# main_v4.net
KiCad netlist of a schematic drawn in EAGLE
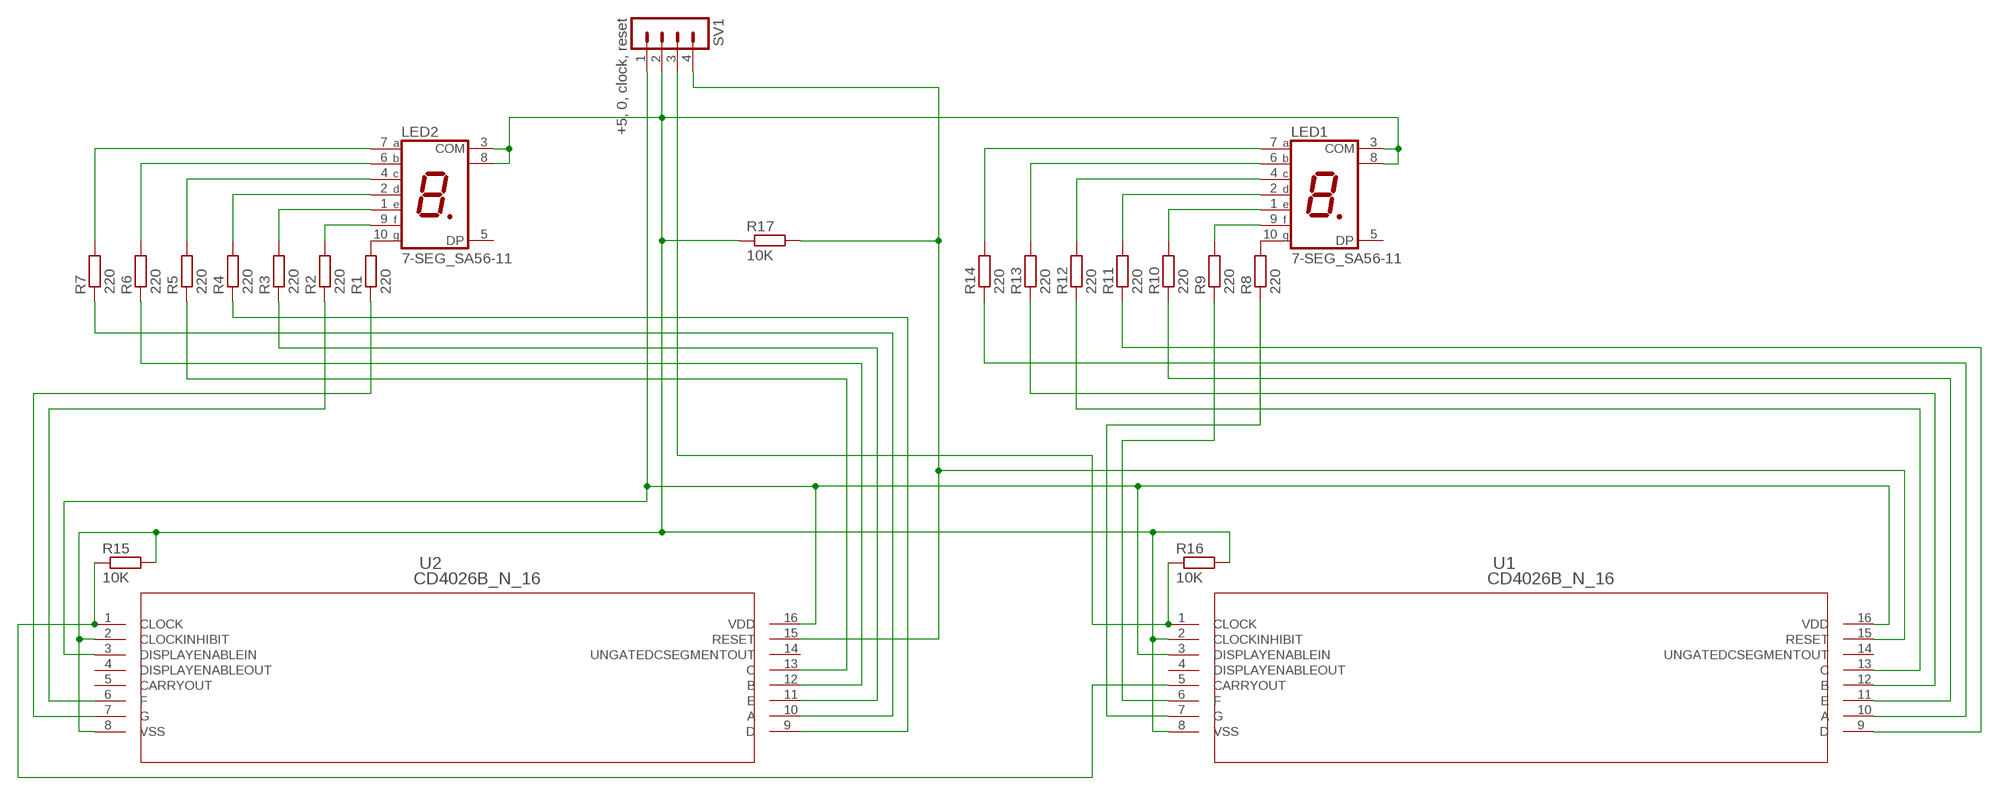
[diagram p0: schematic, sheet 1]

(export (version "E")
  (design (tool "Eeschema 10.0.6"))
  (components
    (comp (ref "LED1")
      (value "7-SEG_SA56-11")
      (footprint "eagle-import:SA56-11")
      (libsource (lib "eagle-import") (part "7-SEG_SA56-11"))
    )
    (comp (ref "LED2")
      (value "7-SEG_SA56-11")
      (footprint "eagle-import:SA56-11")
      (libsource (lib "eagle-import") (part "7-SEG_SA56-11"))
    )
    (comp (ref "R1")
      (value "220")
      (footprint "eagle-import:R0805")
      (libsource (lib "eagle-import") (part "R-EU_R0805"))
    )
    (comp (ref "R2")
      (value "220")
      (footprint "eagle-import:R0805")
      (libsource (lib "eagle-import") (part "R-EU_R0805"))
    )
    (comp (ref "R3")
      (value "220")
      (footprint "eagle-import:R0805")
      (libsource (lib "eagle-import") (part "R-EU_R0805"))
    )
    (comp (ref "R4")
      (value "220")
      (footprint "eagle-import:R0805")
      (libsource (lib "eagle-import") (part "R-EU_R0805"))
    )
    (comp (ref "R5")
      (value "220")
      (footprint "eagle-import:R0805")
      (libsource (lib "eagle-import") (part "R-EU_R0805"))
    )
    (comp (ref "R6")
      (value "220")
      (footprint "eagle-import:R0805")
      (libsource (lib "eagle-import") (part "R-EU_R0805"))
    )
    (comp (ref "R7")
      (value "220")
      (footprint "eagle-import:R0805")
      (libsource (lib "eagle-import") (part "R-EU_R0805"))
    )
    (comp (ref "R8")
      (value "220")
      (footprint "eagle-import:R0805")
      (libsource (lib "eagle-import") (part "R-EU_R0805"))
    )
    (comp (ref "R9")
      (value "220")
      (footprint "eagle-import:R0805")
      (libsource (lib "eagle-import") (part "R-EU_R0805"))
    )
    (comp (ref "R10")
      (value "220")
      (footprint "eagle-import:R0805")
      (libsource (lib "eagle-import") (part "R-EU_R0805"))
    )
    (comp (ref "R11")
      (value "220")
      (footprint "eagle-import:R0805")
      (libsource (lib "eagle-import") (part "R-EU_R0805"))
    )
    (comp (ref "R12")
      (value "220")
      (footprint "eagle-import:R0805")
      (libsource (lib "eagle-import") (part "R-EU_R0805"))
    )
    (comp (ref "R13")
      (value "220")
      (footprint "eagle-import:R0805")
      (libsource (lib "eagle-import") (part "R-EU_R0805"))
    )
    (comp (ref "R14")
      (value "220")
      (footprint "eagle-import:R0805")
      (libsource (lib "eagle-import") (part "R-EU_R0805"))
    )
    (comp (ref "R15")
      (value "10K")
      (footprint "eagle-import:R0805")
      (libsource (lib "eagle-import") (part "R-EU_R0805"))
    )
    (comp (ref "R16")
      (value "10K")
      (footprint "eagle-import:R0805")
      (libsource (lib "eagle-import") (part "R-EU_R0805"))
    )
    (comp (ref "R17")
      (value "10K")
      (footprint "eagle-import:R0805")
      (libsource (lib "eagle-import") (part "R-EU_R0805"))
    )
    (comp (ref "SV1")
      (value "+5, 0, clock, reset")
      (footprint "eagle-import:MA04-1")
      (libsource (lib "eagle-import") (part "MA04-1"))
    )
    (comp (ref "U1")
      (value "CD4026B_N_16")
      (footprint "eagle-import:N16")
      (fields
        (field (name "GENERIC_PART_NUMBER") "CD4026B")
        (field (name "MANUFACTURER") "Texas Instruments")
      )
      (libsource (lib "eagle-import") (part "CD4026B_N_16"))
    )
    (comp (ref "U2")
      (value "CD4026B_N_16")
      (footprint "eagle-import:N16")
      (fields
        (field (name "GENERIC_PART_NUMBER") "CD4026B")
        (field (name "MANUFACTURER") "Texas Instruments")
      )
      (libsource (lib "eagle-import") (part "CD4026B_N_16"))
    )
  )
  (nets
    (net (code "1") (name "Net-(LED1-A)") (class "Default")
      (node (ref "LED1") (pin "7") (pinfunction "A_7") (pintype "passive"))
      (node (ref "R14") (pin "2") (pinfunction "2_2") (pintype "passive"))
    )
    (net (code "2") (name "Net-(LED1-B)") (class "Default")
      (node (ref "LED1") (pin "6") (pinfunction "B_6") (pintype "passive"))
      (node (ref "R13") (pin "2") (pinfunction "2_2") (pintype "passive"))
    )
    (net (code "3") (name "Net-(LED1-C)") (class "Default")
      (node (ref "LED1") (pin "4") (pinfunction "C_4") (pintype "passive"))
      (node (ref "R12") (pin "2") (pinfunction "2_2") (pintype "passive"))
    )
    (net (code "4") (name "Net-(LED1-D)") (class "Default")
      (node (ref "LED1") (pin "2") (pinfunction "D_2") (pintype "passive"))
      (node (ref "R11") (pin "2") (pinfunction "2_2") (pintype "passive"))
    )
    (net (code "5") (name "Net-(LED1-E)") (class "Default")
      (node (ref "LED1") (pin "1") (pinfunction "E_1") (pintype "passive"))
      (node (ref "R10") (pin "2") (pinfunction "2_2") (pintype "passive"))
    )
    (net (code "6") (name "Net-(LED1-F)") (class "Default")
      (node (ref "LED1") (pin "9") (pinfunction "F_9") (pintype "passive"))
      (node (ref "R9") (pin "2") (pinfunction "2_2") (pintype "passive"))
    )
    (net (code "7") (name "Net-(LED1-G)") (class "Default")
      (node (ref "LED1") (pin "10") (pinfunction "G_10") (pintype "passive"))
      (node (ref "R8") (pin "2") (pinfunction "2_2") (pintype "passive"))
    )
    (net (code "8") (name "Net-(LED2-A)") (class "Default")
      (node (ref "LED2") (pin "7") (pinfunction "A_7") (pintype "passive"))
      (node (ref "R7") (pin "2") (pinfunction "2_2") (pintype "passive"))
    )
    (net (code "9") (name "Net-(LED2-B)") (class "Default")
      (node (ref "LED2") (pin "6") (pinfunction "B_6") (pintype "passive"))
      (node (ref "R6") (pin "2") (pinfunction "2_2") (pintype "passive"))
    )
    (net (code "10") (name "Net-(LED2-C)") (class "Default")
      (node (ref "LED2") (pin "4") (pinfunction "C_4") (pintype "passive"))
      (node (ref "R5") (pin "2") (pinfunction "2_2") (pintype "passive"))
    )
    (net (code "11") (name "Net-(LED2-D)") (class "Default")
      (node (ref "LED2") (pin "2") (pinfunction "D_2") (pintype "passive"))
      (node (ref "R4") (pin "2") (pinfunction "2_2") (pintype "passive"))
    )
    (net (code "12") (name "Net-(LED2-E)") (class "Default")
      (node (ref "LED2") (pin "1") (pinfunction "E_1") (pintype "passive"))
      (node (ref "R3") (pin "2") (pinfunction "2_2") (pintype "passive"))
    )
    (net (code "13") (name "Net-(LED2-F)") (class "Default")
      (node (ref "LED2") (pin "9") (pinfunction "F_9") (pintype "passive"))
      (node (ref "R2") (pin "2") (pinfunction "2_2") (pintype "passive"))
    )
    (net (code "14") (name "Net-(LED2-G)") (class "Default")
      (node (ref "LED2") (pin "10") (pinfunction "G_10") (pintype "passive"))
      (node (ref "R1") (pin "2") (pinfunction "2_2") (pintype "passive"))
    )
    (net (code "15") (name "Net-(U1-A)") (class "Default")
      (node (ref "R14") (pin "1") (pinfunction "1_1") (pintype "passive"))
      (node (ref "U1") (pin "10") (pinfunction "A_10") (pintype "passive"))
    )
    (net (code "16") (name "Net-(U1-B)") (class "Default")
      (node (ref "R13") (pin "1") (pinfunction "1_1") (pintype "passive"))
      (node (ref "U1") (pin "12") (pinfunction "B_12") (pintype "passive"))
    )
    (net (code "17") (name "Net-(U1-C)") (class "Default")
      (node (ref "R12") (pin "1") (pinfunction "1_1") (pintype "passive"))
      (node (ref "U1") (pin "13") (pinfunction "C_13") (pintype "passive"))
    )
    (net (code "18") (name "Net-(U1-CARRYOUT)") (class "Default")
      (node (ref "R15") (pin "1") (pinfunction "1_1") (pintype "passive"))
      (node (ref "U1") (pin "5") (pinfunction "CARRYOUT_5") (pintype "output"))
      (node (ref "U2") (pin "1") (pinfunction "CLOCK_1") (pintype "passive"))
    )
    (net (code "19") (name "Net-(U1-CLOCK)") (class "Default")
      (node (ref "R16") (pin "1") (pinfunction "1_1") (pintype "passive"))
      (node (ref "SV1") (pin "3") (pinfunction "3_3") (pintype "passive"))
      (node (ref "U1") (pin "1") (pinfunction "CLOCK_1") (pintype "passive"))
    )
    (net (code "20") (name "Net-(U1-CLOCKINHIBIT)") (class "Default")
      (node (ref "LED1") (pin "3") (pinfunction "COM_3") (pintype "passive"))
      (node (ref "LED1") (pin "8") (pinfunction "COM_8") (pintype "passive"))
      (node (ref "LED2") (pin "3") (pinfunction "COM_3") (pintype "passive"))
      (node (ref "LED2") (pin "8") (pinfunction "COM_8") (pintype "passive"))
      (node (ref "R15") (pin "2") (pinfunction "2_2") (pintype "passive"))
      (node (ref "R16") (pin "2") (pinfunction "2_2") (pintype "passive"))
      (node (ref "R17") (pin "1") (pinfunction "1_1") (pintype "passive"))
      (node (ref "SV1") (pin "2") (pinfunction "2_2") (pintype "passive"))
      (node (ref "U1") (pin "2") (pinfunction "CLOCKINHIBIT_2") (pintype "passive"))
      (node (ref "U1") (pin "8") (pinfunction "VSS_8") (pintype "power_in"))
      (node (ref "U2") (pin "2") (pinfunction "CLOCKINHIBIT_2") (pintype "passive"))
      (node (ref "U2") (pin "8") (pinfunction "VSS_8") (pintype "power_in"))
    )
    (net (code "21") (name "Net-(U1-D)") (class "Default")
      (node (ref "R11") (pin "1") (pinfunction "1_1") (pintype "passive"))
      (node (ref "U1") (pin "9") (pinfunction "D_9") (pintype "passive"))
    )
    (net (code "22") (name "Net-(U1-DISPLAYENABLEIN)") (class "Default")
      (node (ref "SV1") (pin "1") (pinfunction "1_1") (pintype "passive"))
      (node (ref "U1") (pin "16") (pinfunction "VDD_16") (pintype "power_in"))
      (node (ref "U1") (pin "3") (pinfunction "DISPLAYENABLEIN_3") (pintype "input"))
      (node (ref "U2") (pin "16") (pinfunction "VDD_16") (pintype "power_in"))
      (node (ref "U2") (pin "3") (pinfunction "DISPLAYENABLEIN_3") (pintype "input"))
    )
    (net (code "23") (name "Net-(U1-E)") (class "Default")
      (node (ref "R10") (pin "1") (pinfunction "1_1") (pintype "passive"))
      (node (ref "U1") (pin "11") (pinfunction "E_11") (pintype "passive"))
    )
    (net (code "24") (name "Net-(U1-F)") (class "Default")
      (node (ref "R9") (pin "1") (pinfunction "1_1") (pintype "passive"))
      (node (ref "U1") (pin "6") (pinfunction "F_6") (pintype "passive"))
    )
    (net (code "25") (name "Net-(U1-G)") (class "Default")
      (node (ref "R8") (pin "1") (pinfunction "1_1") (pintype "passive"))
      (node (ref "U1") (pin "7") (pinfunction "G_7") (pintype "passive"))
    )
    (net (code "26") (name "Net-(U1-RESET)") (class "Default")
      (node (ref "R17") (pin "2") (pinfunction "2_2") (pintype "passive"))
      (node (ref "SV1") (pin "4") (pinfunction "4_4") (pintype "passive"))
      (node (ref "U1") (pin "15") (pinfunction "RESET_15") (pintype "passive"))
      (node (ref "U2") (pin "15") (pinfunction "RESET_15") (pintype "passive"))
    )
    (net (code "27") (name "Net-(U2-A)") (class "Default")
      (node (ref "R7") (pin "1") (pinfunction "1_1") (pintype "passive"))
      (node (ref "U2") (pin "10") (pinfunction "A_10") (pintype "passive"))
    )
    (net (code "28") (name "Net-(U2-B)") (class "Default")
      (node (ref "R6") (pin "1") (pinfunction "1_1") (pintype "passive"))
      (node (ref "U2") (pin "12") (pinfunction "B_12") (pintype "passive"))
    )
    (net (code "29") (name "Net-(U2-C)") (class "Default")
      (node (ref "R5") (pin "1") (pinfunction "1_1") (pintype "passive"))
      (node (ref "U2") (pin "13") (pinfunction "C_13") (pintype "passive"))
    )
    (net (code "30") (name "Net-(U2-D)") (class "Default")
      (node (ref "R4") (pin "1") (pinfunction "1_1") (pintype "passive"))
      (node (ref "U2") (pin "9") (pinfunction "D_9") (pintype "passive"))
    )
    (net (code "31") (name "Net-(U2-E)") (class "Default")
      (node (ref "R3") (pin "1") (pinfunction "1_1") (pintype "passive"))
      (node (ref "U2") (pin "11") (pinfunction "E_11") (pintype "passive"))
    )
    (net (code "32") (name "Net-(U2-F)") (class "Default")
      (node (ref "R2") (pin "1") (pinfunction "1_1") (pintype "passive"))
      (node (ref "U2") (pin "6") (pinfunction "F_6") (pintype "passive"))
    )
    (net (code "33") (name "Net-(U2-G)") (class "Default")
      (node (ref "R1") (pin "1") (pinfunction "1_1") (pintype "passive"))
      (node (ref "U2") (pin "7") (pinfunction "G_7") (pintype "passive"))
    )
    (net (code "34") (name "unconnected-(LED1-DP-Pad5)") (class "Default")
      (node (ref "LED1") (pin "5") (pinfunction "DP_5") (pintype "passive"))
    )
    (net (code "35") (name "unconnected-(LED2-DP-Pad5)") (class "Default")
      (node (ref "LED2") (pin "5") (pinfunction "DP_5") (pintype "passive"))
    )
    (net (code "36") (name "unconnected-(U1-DISPLAYENABLEOUT-Pad4)") (class "Default")
      (node (ref "U1") (pin "4") (pinfunction "DISPLAYENABLEOUT_4") (pintype "output"))
    )
    (net (code "37") (name "unconnected-(U1-UNGATEDCSEGMENTOUT-Pad14)") (class "Default")
      (node (ref "U1") (pin "14") (pinfunction "UNGATEDCSEGMENTOUT_14") (pintype "output"))
    )
    (net (code "38") (name "unconnected-(U2-CARRYOUT-Pad5)") (class "Default")
      (node (ref "U2") (pin "5") (pinfunction "CARRYOUT_5") (pintype "output"))
    )
    (net (code "39") (name "unconnected-(U2-DISPLAYENABLEOUT-Pad4)") (class "Default")
      (node (ref "U2") (pin "4") (pinfunction "DISPLAYENABLEOUT_4") (pintype "output"))
    )
    (net (code "40") (name "unconnected-(U2-UNGATEDCSEGMENTOUT-Pad14)") (class "Default")
      (node (ref "U2") (pin "14") (pinfunction "UNGATEDCSEGMENTOUT_14") (pintype "output"))
    )
  )
)
